# Pag1_PowerSupply.net
KiCad netlist of a schematic drawn in Altium Designer
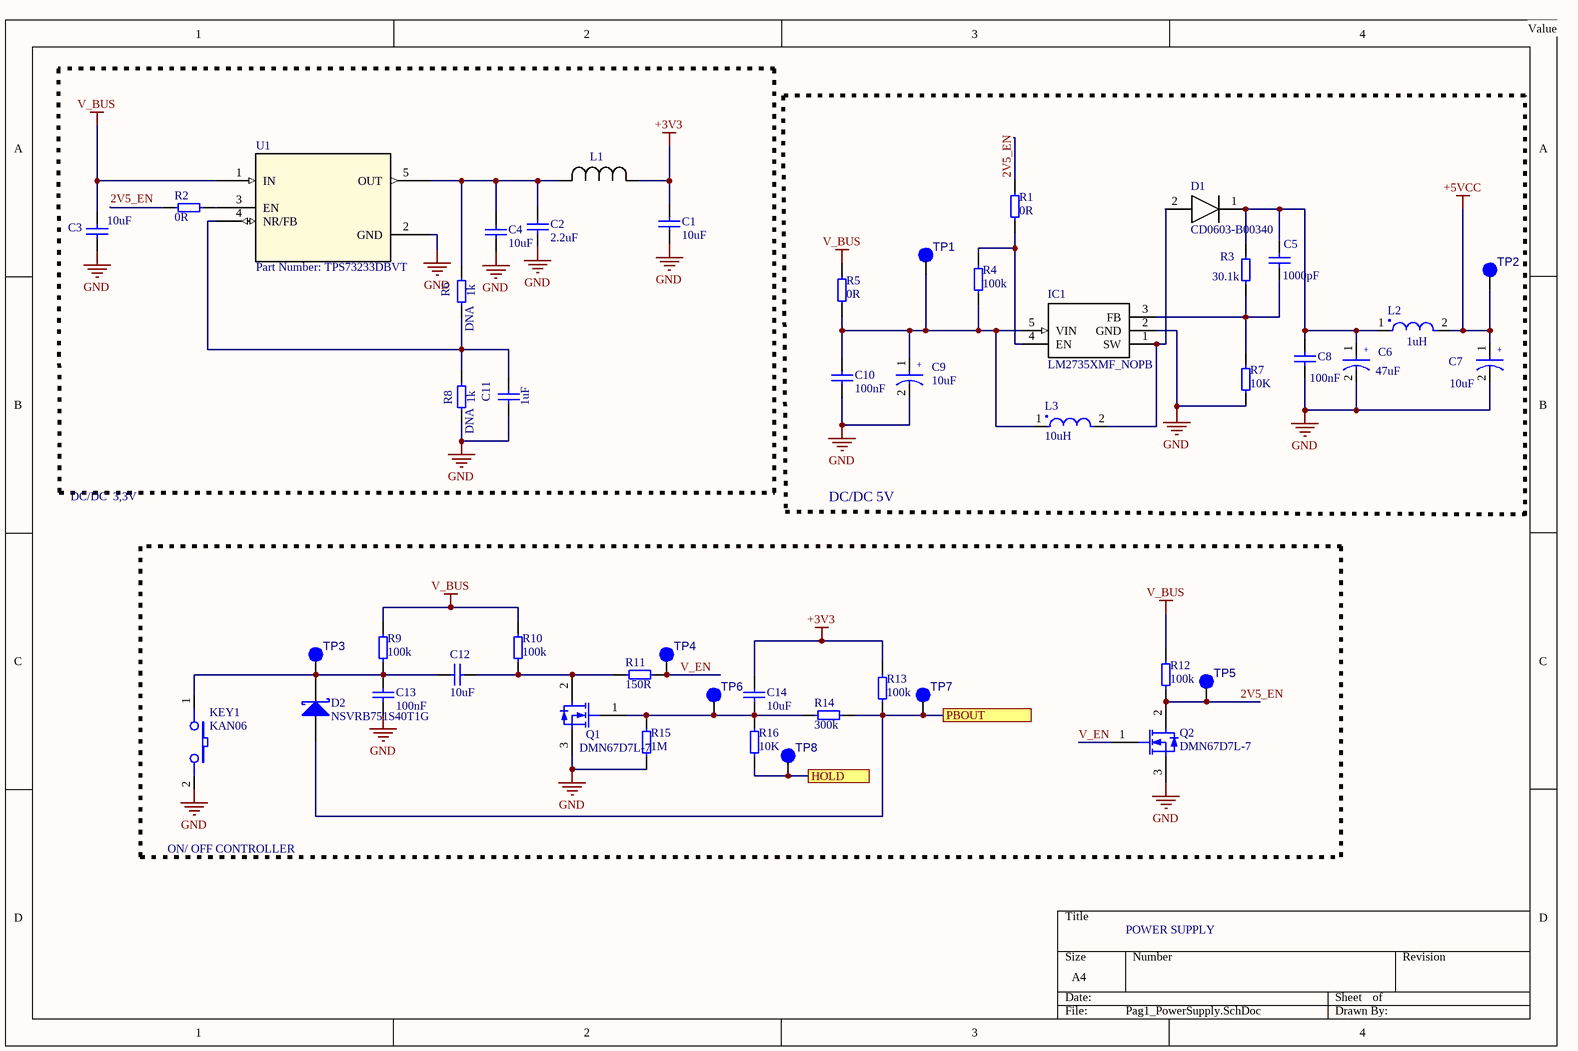
[diagram p0: Pag1_PowerSupply.SchDoc]

(export (version "E")
  (design (tool "Eeschema 10.0.6"))
  (components
    (comp (ref "C1")
      (value "10uF")
      (footprint "0603")
      (description "Multilayer Ceramic Capacitors MLCC - SMD/SMT 10uF 0603 10V 10%")
      (fields (field (name "MANUFACTURER") "Murata Electronics") (field (name "MPN") "GRM188R61A106KE69D"))
      (libsource (lib "LIBSCH_PULLUP") (part "Cap"))
    )
    (comp (ref "C2")
      (value "2.2uF")
      (footprint "0603")
      (description "Multilayer Ceramic Capacitors MLCC - SMD/SMT 2.2uF 0603 16V 20%")
      (fields (field (name "MANUFACTURER") "Wurth Electronics") (field (name "MPN") "885012106018"))
      (libsource (lib "Database_Pullup") (part "Cap"))
    )
    (comp (ref "C3")
      (value "10uF")
      (footprint "0603")
      (description "Multilayer Ceramic Capacitors MLCC - SMD/SMT 10uF 0603 10V 10%")
      (fields (field (name "MANUFACTURER") "Murata Electronics") (field (name "MPN") "GRM188R61A106KE69D"))
      (libsource (lib "Database_Pullup") (part "Cap"))
    )
    (comp (ref "C4")
      (value "10uF")
      (footprint "0603")
      (description "Multilayer Ceramic Capacitors MLCC - SMD/SMT 10uF 0603 10V 10%")
      (fields (field (name "MANUFACTURER") "Murata Electronics") (field (name "MPN") "GRM188R61A106KE69D"))
      (libsource (lib "LIBSCH_PULLUP") (part "Cap"))
    )
    (comp (ref "C5")
      (value "1000pF")
      (footprint "0603")
      (description "Capacitor Ceramic 1000pF 10% 16V 0603 (1608 Metric)")
      (fields (field (name "MPN") "06033C102KAT2A") (field (name "MANUFACTURER") "Kyocera AVX"))
      (libsource (lib "LIBSCH_PULLUP") (part "Cap_1"))
    )
    (comp (ref "C6")
      (value "47uF")
      (footprint "0805")
      (description "Multilayer Ceramic Capacitors MLCC - SMD/SMT 47uF 0805 10V 20%")
      (fields (field (name "MANUFACTURER") "Murata Electronics") (field (name "MPN") "GRM21BR61A476ME15K"))
      (libsource (lib "LIBSCH_PULLUP") (part "Cap Pol"))
    )
    (comp (ref "C7")
      (value "10uF")
      (footprint "CAP_6.6X6.6")
      (description "Capacitor Electrolytic 10uF 20% 16V")
      (fields (field (name "MPN") "UUQ1C100MCL1GB") (field (name "MANUFACTURER") "Murata Electronics"))
      (libsource (lib "LIBSCH_PULLUP (Cópia em conflito de Engenharia Pullup 2018-04-18)") (part "Cap Pol_1"))
    )
    (comp (ref "C8")
      (value "100nF")
      (footprint "0603")
      (description "Multilayer Ceramic Capacitors MLCC - SMD/SMT 100nF 16V 0603 10%")
      (fields (field (name "MPN") "C0603C104K4RACTU") (field (name "MANUFACTURER") "Kemet"))
      (libsource (lib "LIBSCH_PULLUP") (part "Cap_1"))
    )
    (comp (ref "C9")
      (value "10uF")
      (footprint "CAP_6.6X6.6")
      (description "Capacitor Electrolytic 10uF 20% 16V")
      (fields (field (name "MPN") "UUQ1C100MCL1GB") (field (name "MANUFACTURER") "Murata Electronics"))
      (libsource (lib "LIBSCH_PULLUP (Cópia em conflito de Engenharia Pullup 2018-04-18)") (part "Cap Pol_1"))
    )
    (comp (ref "C10")
      (value "100nF")
      (footprint "0603")
      (description "Multilayer Ceramic Capacitors MLCC - SMD/SMT 100nF 16V 0603 10%")
      (fields (field (name "MPN") "C0603C104K4RACTU") (field (name "MANUFACTURER") "Kemet"))
      (libsource (lib "LIBSCH_PULLUP") (part "Cap_1"))
    )
    (comp (ref "C11")
      (value "1uF")
      (footprint "0603")
      (description "Multilayer Ceramic Capacitors MLCC - SMD/SMT 1uF 25V 0603 10%")
      (fields
        (field (name "MANUFACTURER") "Samsung Electro-Mechanics")
        (field (name "MPN") "CL10A105KA8NNNC")
      )
      (libsource (lib "Database_Pullup") (part "Cap"))
    )
    (comp (ref "C12")
      (value "10uF")
      (footprint "0603")
      (description "Multilayer Ceramic Capacitors MLCC - SMD/SMT 10uF 0603 10V 10%")
      (fields (field (name "MPN") "GRM188R61A106KE69D") (field (name "MANUFACTURER") "Murata Electronics"))
      (libsource (lib "SchLib1") (part "Cap"))
    )
    (comp (ref "C13")
      (value "100nF")
      (footprint "0603")
      (description "Multilayer Ceramic Capacitors MLCC - SMD/SMT 100nF 16V 0603 10%")
      (fields (field (name "MPN") "C0603C104K4RACTU") (field (name "MANUFACTURER") "Kemet"))
      (libsource (lib "LIBSCH_PULLUP") (part "Cap_1"))
    )
    (comp (ref "C14")
      (value "10uF")
      (footprint "0603")
      (description "Multilayer Ceramic Capacitors MLCC - SMD/SMT 10uF 0603 10V 10%")
      (fields (field (name "MPN") "GRM188R61A106KE69D") (field (name "MANUFACTURER") "Murata Electronics"))
      (libsource (lib "SchLib1") (part "Cap"))
    )
    (comp (ref "D1")
      (value "CD0603-B00340")
      (footprint "DIOM179X85N")
      (description "Diode")
      (fields (field (name "MPN") "CDBU0130R") (field (name "MANUFACTURER") "Comchip Technology"))
      (libsource (lib "CD0603") (part "CD0603-B00340"))
    )
    (comp (ref "D2")
      (value "NSVRB751S40T1G")
      (footprint "D_SOD523")
      (description "Schottky Diodes & Rectifiers SS 40V SHTKY SOD523")
      (fields (field (name "MANUFACTURER") "onsemi"))
      (libsource (lib "SchLib1") (part "Schottky Diode"))
    )
    (comp (ref "IC1")
      (value "LM2735XMF_NOPB")
      (footprint "SOT95P280X145-5N")
      (description "Integrated Circuit")
      (fields (field (name "MPN") "LM2735XMF/NOPB") (field (name "MANUFACTURER") "Texas Instruments"))
      (libsource (lib "LM2735") (part "LM2735XMF_NOPB"))
    )
    (comp (ref "KEY1")
      (value "KAN06")
      (footprint "KAN06_v2")
      (fields (field (name "MANUFACTURER") "Metaltex"))
      (libsource (lib "LIBSCH_PULLUP") (part "SDS"))
    )
    (comp (ref "L1")
      (value "Part Number: MLZ2012A3R3WT000")
      (footprint "IND_2012")
      (description "No Description Available")
      (fields (field (name "MPN") "MLZ2012A3R3WT000") (field (name "MANUFACTURER") "TDK"))
      (libsource (lib "LIBSCH_PULLUP") (part "MLZ2012A3R3WT000"))
    )
    (comp (ref "L2")
      (value "1uH")
      (footprint "SRP4012TA")
      (description "Power Inductors - SMD 1uH 20% SMD 4012 AEC-Q200")
      (fields (field (name "MANUFACTURER") "Bourns") (field (name "MPN") "SRP4012TA-1R0M"))
      (libsource (lib "potenciostato") (part "IC_1uH"))
    )
    (comp (ref "L3")
      (value "10uH")
      (footprint "SRP4012TA")
      (description "Power Inductors - SMD 10uH 20% SMD 4012 AEC-Q200")
      (fields (field (name "MANUFACTURER") "Bourns") (field (name "MPN") "SRP4012TA-100M"))
      (libsource (lib "potenciostato") (part "IC_1uH"))
    )
    (comp (ref "Q1")
      (value "DMN67D7L-7")
      (footprint "D_SOT23")
      (description "MOSFET BVDSS: 41V-60V")
      (fields (field (name "MANUFACTURER") "Diodes Incorporated"))
      (libsource (lib "SchLib1") (part "MOSFET N-Ch"))
    )
    (comp (ref "Q2")
      (value "DMN67D7L-7")
      (footprint "D_SOT23")
      (description "MOSFET BVDSS: 41V-60V")
      (fields (field (name "MANUFACTURER") "Diodes Incorporated"))
      (libsource (lib "SchLib1") (part "MOSFET N-Ch"))
    )
    (comp (ref "R1")
      (value "0R")
      (footprint "0603")
      (description "Thick Film Resistors - SMD 0 Ohms 100 mW 0603 5%")
      (fields (field (name "MPN") "RC0603JR-070RL") (field (name "MANUFACTURER") "Yageo"))
      (libsource (lib "LIBSCH_PULLUP") (part "Res_1"))
    )
    (comp (ref "R2")
      (value "0R")
      (footprint "0603")
      (description "Thick Film Resistors - SMD 0 Ohms 100 mW 0603 5%")
      (fields (field (name "MPN") "RC0603JR-070RL") (field (name "MANUFACTURER") "Yageo"))
      (libsource (lib "SchLib1") (part "Res"))
    )
    (comp (ref "R3")
      (value "30.1k")
      (footprint "0603")
      (description "Resistor Thick Film 30.1k 1% 0.1W, 1/10W 0603 (1608 metric) +/- 100 PPM / K")
      (fields (field (name "MPN") "RC0603FR-0730K1L") (field (name "MANUFACTURER") "Yageo"))
      (libsource (lib "LIBSCH_PULLUP") (part "Res_1"))
    )
    (comp (ref "R4")
      (value "100k")
      (footprint "0603")
      (description "Thick Film Resistors - SMD 100 kOhms 0603 100mW 1%")
      (fields (field (name "MPN") "RC0603FR-07100KL") (field (name "MANUFACTURER") "Yageo"))
      (libsource (lib "LIBSCH_PULLUP") (part "Res_1"))
    )
    (comp (ref "R5")
      (value "0R")
      (footprint "0603")
      (description "Thick Film Resistors - SMD 0 Ohms 100 mW 0603 5%")
      (fields (field (name "MPN") "RC0603JR-070RL") (field (name "MANUFACTURER") "Yageo"))
      (libsource (lib "LIBSCH_PULLUP") (part "Res_1"))
    )
    (comp (ref "R6")
      (value "1k")
      (footprint "0603")
      (description "Thick Film Resistors - SMD 1 kOhms 100 mW 0603 5%")
      (fields
        (field (name "MPN") "RC0603JR-071KL")
        (field (name "MANUFACTURER") "Yageo")
        (field (name "PCBA") "DNA")
      )
      (libsource (lib "Database_Pullup_New") (part "Res"))
    )
    (comp (ref "R7")
      (value "10K")
      (footprint "0603")
      (description "Thick Film Resistors - SMD 10 kOhms 100-200 mW 0603 1%")
      (fields (field (name "MPN") "RC0603FR-1310KL") (field (name "MANUFACTURER") "Yageo"))
      (libsource (lib "LIBSCH_PULLUP") (part "Res_1"))
    )
    (comp (ref "R8")
      (value "1k")
      (footprint "0603")
      (description "Thick Film Resistors - SMD 1 kOhms 100 mW 0603 5%")
      (fields
        (field (name "MPN") "RC0603JR-071KL")
        (field (name "MANUFACTURER") "Yageo")
        (field (name "PCBA") "DNA")
      )
      (libsource (lib "Database_Pullup_New") (part "Res"))
    )
    (comp (ref "R9")
      (value "100k")
      (footprint "0603")
      (description "Thick Film Resistors - SMD 100 kOhms 0603 100mW 1%")
      (fields (field (name "MPN") "RC0603FR-07100KL") (field (name "MANUFACTURER") "YAGEO"))
      (libsource (lib "LIBSCH_PULLUP") (part "Res_1"))
    )
    (comp (ref "R10")
      (value "100k")
      (footprint "0603")
      (description "Thick Film Resistors - SMD 100 kOhms 0603 100mW 1%")
      (fields (field (name "MPN") "RC0603FR-07100KL") (field (name "MANUFACTURER") "YAGEO"))
      (libsource (lib "LIBSCH_PULLUP") (part "Res_1"))
    )
    (comp (ref "R11")
      (value "150R")
      (footprint "0603")
      (description "Thick Film Resistors - SMD 150 Ohms 0603 100mW 5%")
      (fields (field (name "MPN") "CR0603-JW-151ELF") (field (name "MANUFACTURER") "Bourns"))
      (libsource (lib "SchLib1") (part "Res"))
    )
    (comp (ref "R12")
      (value "100k")
      (footprint "0603")
      (description "Thick Film Resistors - SMD 100 kOhms 0603 100mW 1%")
      (fields (field (name "MPN") "RC0603FR-07100KL") (field (name "MANUFACTURER") "YAGEO"))
      (libsource (lib "") (part "Res_2"))
    )
    (comp (ref "R13")
      (value "100k")
      (footprint "0603")
      (description "Thick Film Resistors - SMD 100 kOhms 0603 100mW 1%")
      (fields (field (name "MPN") "RC0603FR-07100KL") (field (name "MANUFACTURER") "YAGEO"))
      (libsource (lib "") (part "Res_2"))
    )
    (comp (ref "R14")
      (value "300k")
      (footprint "0603")
      (description "Thick Film Resistors - SMD 300 kOhms 0603 100mW 1%")
      (fields (field (name "MPN") "RC0603FR-07300KL") (field (name "MANUFACTURER") "Yageo"))
      (libsource (lib "") (part "Res_3"))
    )
    (comp (ref "R15")
      (value "1M")
      (footprint "0603")
      (description "Thick Film Resistors - SMD 1 MOhms 100mW 0603 1%")
      (fields (field (name "MPN") "RC0603FR-071ML") (field (name "MANUFACTURER") "Yageo"))
      (libsource (lib "") (part "Res_1"))
    )
    (comp (ref "R16")
      (value "10K")
      (footprint "0603")
      (description "Thick Film Resistors - SMD 10 kOhms 100-200 mW 0603 1%")
      (fields (field (name "MPN") "RC0603FR-1310KL") (field (name "MANUFACTURER") "Yageo"))
      (libsource (lib "") (part "Res_1"))
    )
    (comp (ref "TP1")
      (value "Test Point")
      (footprint "TEST")
      (fields (field (name "MPN") "Test_Point") (field (name "MANUFACTURER") "DNA"))
      (libsource (lib "SchLib1") (part "TESTPOINT"))
    )
    (comp (ref "TP2")
      (value "Test Point")
      (footprint "TEST")
      (fields (field (name "MPN") "Test_Point") (field (name "MANUFACTURER") "DNA"))
      (libsource (lib "SchLib1") (part "TESTPOINT"))
    )
    (comp (ref "TP3")
      (value "Test Point")
      (footprint "TEST")
      (fields (field (name "MPN") "Test_Point") (field (name "MANUFACTURER") "DNA"))
      (libsource (lib "SchLib1") (part "TESTPOINT"))
    )
    (comp (ref "TP4")
      (value "Test Point")
      (footprint "TEST")
      (fields (field (name "MPN") "Test_Point") (field (name "MANUFACTURER") "DNA"))
      (libsource (lib "SchLib1") (part "TESTPOINT"))
    )
    (comp (ref "TP5")
      (value "Test Point")
      (footprint "TEST")
      (fields (field (name "MPN") "Test_Point") (field (name "MANUFACTURER") "DNA"))
      (libsource (lib "SchLib1") (part "TESTPOINT"))
    )
    (comp (ref "TP6")
      (value "Test Point")
      (footprint "TEST")
      (fields (field (name "MPN") "Test_Point") (field (name "MANUFACTURER") "DNA"))
      (libsource (lib "SchLib1") (part "TESTPOINT"))
    )
    (comp (ref "TP7")
      (value "Test Point")
      (footprint "TEST")
      (fields (field (name "MPN") "Test_Point") (field (name "MANUFACTURER") "DNA"))
      (libsource (lib "SchLib1") (part "TESTPOINT"))
    )
    (comp (ref "TP8")
      (value "Test Point")
      (footprint "TEST")
      (fields (field (name "MPN") "Test_Point") (field (name "MANUFACTURER") "DNA"))
      (libsource (lib "SchLib1") (part "TESTPOINT"))
    )
    (comp (ref "U1")
      (value "Part Number: TPS73233DBVT")
      (footprint "DBV5")
      (description "LDO Voltage Regulators Cap-Free NMOS 250mA")
      (fields (field (name "MANUFACTURER") "Texas Instruments") (field (name "MPN") "TPS73233DBVR"))
      (libsource (lib "LIBSCH_PULLUP") (part "TPS73225DBVT"))
    )
  )
  (nets
    (net (code "1") (name "+3V3") (class "Default")
      (node (ref "C1") (pin "2") (pinfunction "2_2") (pintype "passive"))
      (node (ref "C14") (pin "1") (pinfunction "1_1") (pintype "passive"))
      (node (ref "L1") (pin "1") (pinfunction "1_1") (pintype "passive"))
      (node (ref "R13") (pin "2") (pinfunction "2_2") (pintype "passive"))
    )
    (net (code "2") (name "+5VCC") (class "Default")
      (node (ref "C7") (pin "1") (pinfunction "1_1") (pintype "passive"))
      (node (ref "L2") (pin "2") (pinfunction "2_2") (pintype "passive"))
      (node (ref "TP2") (pin "1") (pinfunction "TP_1") (pintype "passive"))
    )
    (net (code "3") (name "/2V5_EN") (class "Default")
      (node (ref "Q2") (pin "2") (pinfunction "D_2") (pintype "passive"))
      (node (ref "R1") (pin "2") (pinfunction "2_2") (pintype "passive"))
      (node (ref "R12") (pin "1") (pinfunction "1_1") (pintype "passive"))
      (node (ref "R2") (pin "2") (pinfunction "2_2") (pintype "passive"))
      (node (ref "TP5") (pin "1") (pinfunction "TP_1") (pintype "passive"))
    )
    (net (code "4") (name "/HOLD") (class "Default")
      (node (ref "R16") (pin "2") (pinfunction "2_2") (pintype "passive"))
      (node (ref "TP8") (pin "1") (pinfunction "TP_1") (pintype "passive"))
    )
    (net (code "5") (name "/PBOUT") (class "Default")
      (node (ref "D2") (pin "A") (pinfunction "A_A") (pintype "passive"))
      (node (ref "R13") (pin "1") (pinfunction "1_1") (pintype "passive"))
      (node (ref "R14") (pin "2") (pinfunction "2_2") (pintype "passive"))
      (node (ref "TP7") (pin "1") (pinfunction "TP_1") (pintype "passive"))
    )
    (net (code "6") (name "/V_EN") (class "Default")
      (node (ref "Q2") (pin "1") (pinfunction "G_1") (pintype "passive"))
      (node (ref "R11") (pin "1") (pinfunction "1_1") (pintype "passive"))
      (node (ref "TP4") (pin "1") (pinfunction "TP_1") (pintype "passive"))
    )
    (net (code "7") (name "GND") (class "Default")
      (node (ref "C1") (pin "1") (pinfunction "1_1") (pintype "passive"))
      (node (ref "C10") (pin "1") (pinfunction "1_1") (pintype "passive"))
      (node (ref "C11") (pin "1") (pinfunction "1_1") (pintype "passive"))
      (node (ref "C13") (pin "1") (pinfunction "1_1") (pintype "passive"))
      (node (ref "C2") (pin "1") (pinfunction "1_1") (pintype "passive"))
      (node (ref "C3") (pin "1") (pinfunction "1_1") (pintype "passive"))
      (node (ref "C4") (pin "1") (pinfunction "1_1") (pintype "passive"))
      (node (ref "C6") (pin "2") (pinfunction "2_2") (pintype "passive"))
      (node (ref "C7") (pin "2") (pinfunction "2_2") (pintype "passive"))
      (node (ref "C8") (pin "1") (pinfunction "1_1") (pintype "passive"))
      (node (ref "C9") (pin "2") (pinfunction "2_2") (pintype "passive"))
      (node (ref "IC1") (pin "2") (pinfunction "GND_2") (pintype "power_in"))
      (node (ref "KEY1") (pin "2") (pinfunction "2_2") (pintype "passive"))
      (node (ref "Q1") (pin "3") (pinfunction "S_3") (pintype "passive"))
      (node (ref "Q2") (pin "3") (pinfunction "S_3") (pintype "passive"))
      (node (ref "R15") (pin "2") (pinfunction "2_2") (pintype "passive"))
      (node (ref "R7") (pin "1") (pinfunction "1_1") (pintype "passive"))
      (node (ref "R8") (pin "2") (pinfunction "2_2") (pintype "passive"))
      (node (ref "U1") (pin "2") (pinfunction "GND_2") (pintype "power_in"))
    )
    (net (code "8") (name "Net-(D1-A)") (class "Default")
      (node (ref "D1") (pin "2") (pinfunction "A_2") (pintype "passive"))
      (node (ref "IC1") (pin "1") (pinfunction "SW_1") (pintype "passive"))
      (node (ref "L3") (pin "2") (pinfunction "2_2") (pintype "passive"))
    )
    (net (code "9") (name "Net-(D1-K)") (class "Default")
      (node (ref "C5") (pin "2") (pinfunction "2_2") (pintype "passive"))
      (node (ref "C6") (pin "1") (pinfunction "1_1") (pintype "passive"))
      (node (ref "C8") (pin "2") (pinfunction "2_2") (pintype "passive"))
      (node (ref "D1") (pin "1") (pinfunction "K_1") (pintype "passive"))
      (node (ref "L2") (pin "1") (pinfunction "1_1") (pintype "passive"))
      (node (ref "R3") (pin "2") (pinfunction "2_2") (pintype "passive"))
    )
    (net (code "10") (name "Net-(IC1-EN)") (class "Default")
      (node (ref "IC1") (pin "4") (pinfunction "EN_4") (pintype "passive"))
      (node (ref "R1") (pin "1") (pinfunction "1_1") (pintype "passive"))
      (node (ref "R4") (pin "2") (pinfunction "2_2") (pintype "passive"))
    )
    (net (code "11") (name "Net-(IC1-FB)") (class "Default")
      (node (ref "C5") (pin "1") (pinfunction "1_1") (pintype "passive"))
      (node (ref "IC1") (pin "3") (pinfunction "FB_3") (pintype "passive"))
      (node (ref "R3") (pin "1") (pinfunction "1_1") (pintype "passive"))
      (node (ref "R7") (pin "2") (pinfunction "2_2") (pintype "passive"))
    )
    (net (code "12") (name "Net-(IC1-VIN)") (class "Default")
      (node (ref "C10") (pin "2") (pinfunction "2_2") (pintype "passive"))
      (node (ref "C9") (pin "1") (pinfunction "1_1") (pintype "passive"))
      (node (ref "IC1") (pin "5") (pinfunction "VIN_5") (pintype "input"))
      (node (ref "L3") (pin "1") (pinfunction "1_1") (pintype "passive"))
      (node (ref "R4") (pin "1") (pinfunction "1_1") (pintype "passive"))
      (node (ref "R5") (pin "1") (pinfunction "1_1") (pintype "passive"))
      (node (ref "TP1") (pin "1") (pinfunction "TP_1") (pintype "passive"))
    )
    (net (code "13") (name "Net-(Q1-D)") (class "Default")
      (node (ref "C12") (pin "1") (pinfunction "1_1") (pintype "passive"))
      (node (ref "Q1") (pin "2") (pinfunction "D_2") (pintype "passive"))
      (node (ref "R10") (pin "1") (pinfunction "1_1") (pintype "passive"))
      (node (ref "R11") (pin "2") (pinfunction "2_2") (pintype "passive"))
    )
    (net (code "14") (name "Net-(Q1-G)") (class "Default")
      (node (ref "C14") (pin "2") (pinfunction "2_2") (pintype "passive"))
      (node (ref "Q1") (pin "1") (pinfunction "G_1") (pintype "passive"))
      (node (ref "R14") (pin "1") (pinfunction "1_1") (pintype "passive"))
      (node (ref "R15") (pin "1") (pinfunction "1_1") (pintype "passive"))
      (node (ref "R16") (pin "1") (pinfunction "1_1") (pintype "passive"))
      (node (ref "TP6") (pin "1") (pinfunction "TP_1") (pintype "passive"))
    )
    (net (code "15") (name "Net-(TP3-TP)") (class "Default")
      (node (ref "C12") (pin "2") (pinfunction "2_2") (pintype "passive"))
      (node (ref "C13") (pin "2") (pinfunction "2_2") (pintype "passive"))
      (node (ref "D2") (pin "K") (pinfunction "K_K") (pintype "passive"))
      (node (ref "KEY1") (pin "1") (pinfunction "1_1") (pintype "passive"))
      (node (ref "R9") (pin "1") (pinfunction "1_1") (pintype "passive"))
      (node (ref "TP3") (pin "1") (pinfunction "TP_1") (pintype "passive"))
    )
    (net (code "16") (name "Net-(U1-EN)") (class "Default")
      (node (ref "R2") (pin "1") (pinfunction "1_1") (pintype "passive"))
      (node (ref "U1") (pin "3") (pinfunction "EN_3") (pintype "passive"))
    )
    (net (code "17") (name "Net-(U1-NR{slash}FB)") (class "Default")
      (node (ref "C11") (pin "2") (pinfunction "2_2") (pintype "passive"))
      (node (ref "R6") (pin "2") (pinfunction "2_2") (pintype "passive"))
      (node (ref "R8") (pin "1") (pinfunction "1_1") (pintype "passive"))
      (node (ref "U1") (pin "4") (pinfunction "NR/FB_4") (pintype "bidirectional"))
    )
    (net (code "18") (name "Net-(U1-OUT)") (class "Default")
      (node (ref "C2") (pin "2") (pinfunction "2_2") (pintype "passive"))
      (node (ref "C4") (pin "2") (pinfunction "2_2") (pintype "passive"))
      (node (ref "L1") (pin "2") (pinfunction "2_2") (pintype "passive"))
      (node (ref "R6") (pin "1") (pinfunction "1_1") (pintype "passive"))
      (node (ref "U1") (pin "5") (pinfunction "OUT_5") (pintype "output"))
    )
    (net (code "19") (name "V_BUS") (class "Default")
      (node (ref "C3") (pin "2") (pinfunction "2_2") (pintype "passive"))
      (node (ref "R10") (pin "2") (pinfunction "2_2") (pintype "passive"))
      (node (ref "R12") (pin "2") (pinfunction "2_2") (pintype "passive"))
      (node (ref "R5") (pin "2") (pinfunction "2_2") (pintype "passive"))
      (node (ref "R9") (pin "2") (pinfunction "2_2") (pintype "passive"))
      (node (ref "U1") (pin "1") (pinfunction "IN_1") (pintype "input"))
    )
  )
)
